# Relay_Schematic_w_headers.net
KiCad netlist of a schematic drawn in Altium Designer
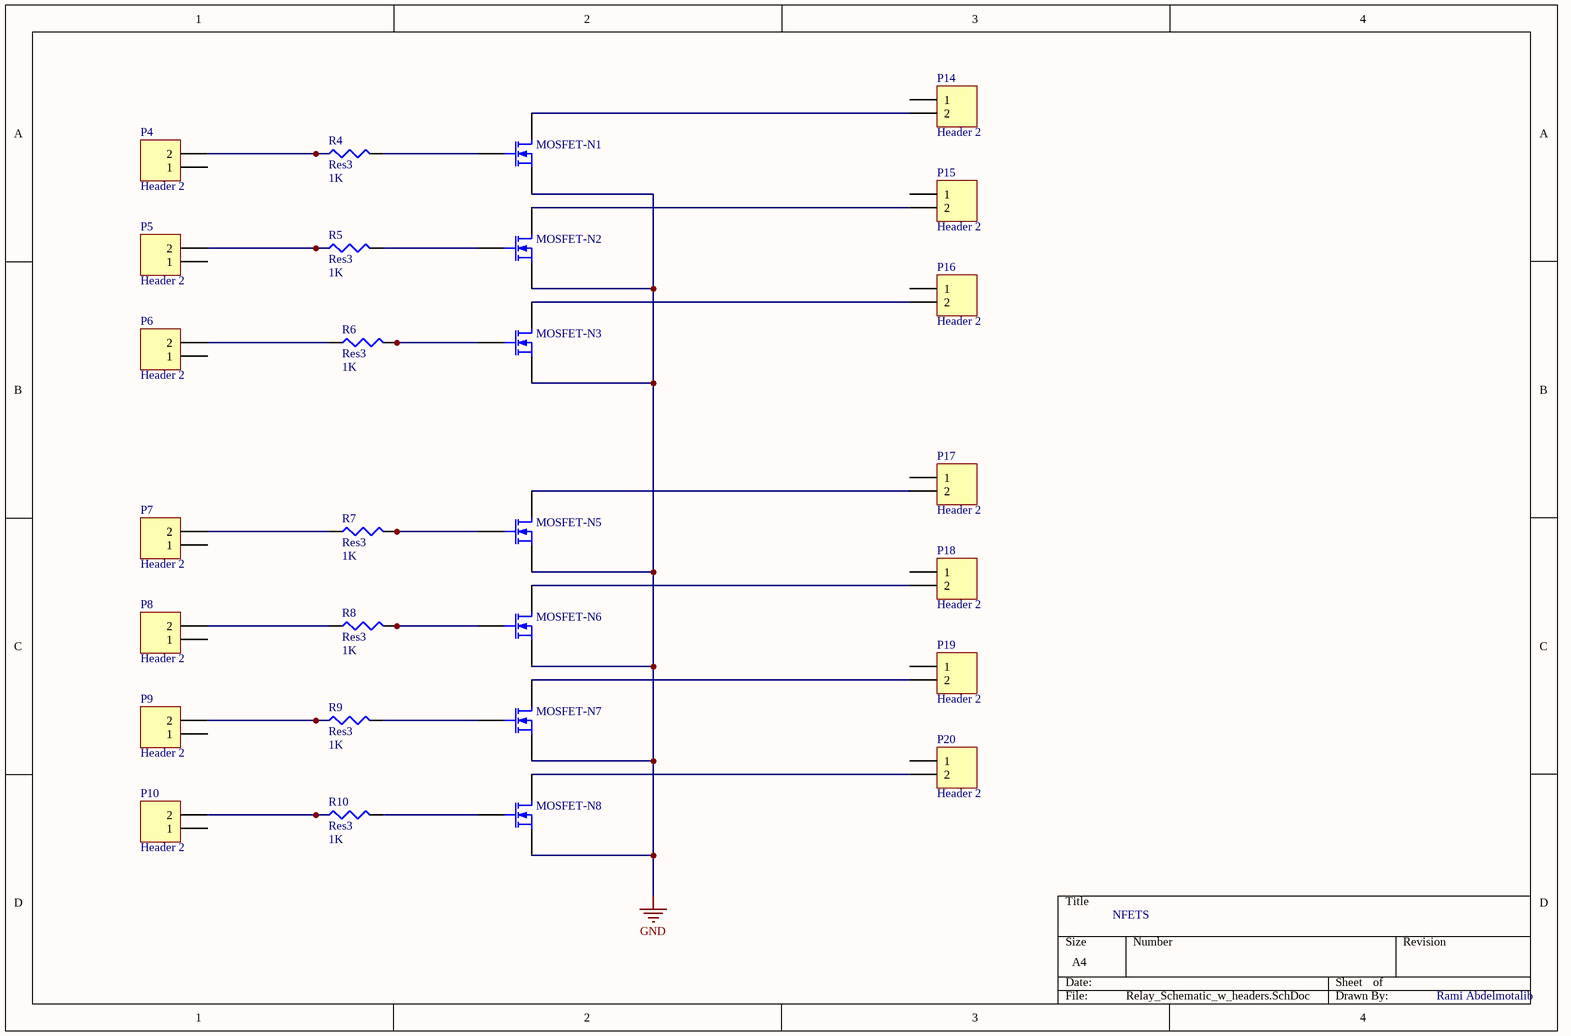
[diagram p0: Relay_Schematic_w_headers.SchDoc]

(export (version "E")
  (design (tool "Eeschema 10.0.6"))
  (components
    (comp (ref "MOSFET-N1")
      (value "~")
      (footprint "E3")
      (description "N-Channel MOSFET")
      (fields (field (name "PUBLISHER") "Altium Limited"))
      (libsource (lib "Miscellaneous Devices") (part "MOSFET-N"))
    )
    (comp (ref "MOSFET-N2")
      (value "~")
      (footprint "E3")
      (description "N-Channel MOSFET")
      (fields (field (name "PUBLISHER") "Altium Limited"))
      (libsource (lib "Miscellaneous Devices") (part "MOSFET-N"))
    )
    (comp (ref "MOSFET-N3")
      (value "~")
      (footprint "E3")
      (description "N-Channel MOSFET")
      (fields (field (name "PUBLISHER") "Altium Limited"))
      (libsource (lib "Miscellaneous Devices") (part "MOSFET-N"))
    )
    (comp (ref "MOSFET-N5")
      (value "~")
      (footprint "E3")
      (description "N-Channel MOSFET")
      (fields (field (name "PUBLISHER") "Altium Limited"))
      (libsource (lib "Miscellaneous Devices") (part "MOSFET-N"))
    )
    (comp (ref "MOSFET-N6")
      (value "~")
      (footprint "E3")
      (description "N-Channel MOSFET")
      (fields (field (name "PUBLISHER") "Altium Limited"))
      (libsource (lib "Miscellaneous Devices") (part "MOSFET-N"))
    )
    (comp (ref "MOSFET-N7")
      (value "~")
      (footprint "E3")
      (description "N-Channel MOSFET")
      (fields (field (name "PUBLISHER") "Altium Limited"))
      (libsource (lib "Miscellaneous Devices") (part "MOSFET-N"))
    )
    (comp (ref "MOSFET-N8")
      (value "~")
      (footprint "E3")
      (description "N-Channel MOSFET")
      (fields (field (name "PUBLISHER") "Altium Limited"))
      (libsource (lib "Miscellaneous Devices") (part "MOSFET-N"))
    )
    (comp (ref "P4")
      (value "Header 2")
      (footprint "HDR1X2")
      (description "Header, 2-Pin")
      (fields (field (name "PUBLISHER") "Altium Limited"))
      (libsource (lib "Miscellaneous Connectors") (part "Header 2"))
    )
    (comp (ref "P5")
      (value "Header 2")
      (footprint "HDR1X2")
      (description "Header, 2-Pin")
      (fields (field (name "PUBLISHER") "Altium Limited"))
      (libsource (lib "Miscellaneous Connectors") (part "Header 2"))
    )
    (comp (ref "P6")
      (value "Header 2")
      (footprint "HDR1X2")
      (description "Header, 2-Pin")
      (fields (field (name "PUBLISHER") "Altium Limited"))
      (libsource (lib "Miscellaneous Connectors") (part "Header 2"))
    )
    (comp (ref "P7")
      (value "Header 2")
      (footprint "HDR1X2")
      (description "Header, 2-Pin")
      (fields (field (name "PUBLISHER") "Altium Limited"))
      (libsource (lib "Miscellaneous Connectors") (part "Header 2"))
    )
    (comp (ref "P8")
      (value "Header 2")
      (footprint "HDR1X2")
      (description "Header, 2-Pin")
      (fields (field (name "PUBLISHER") "Altium Limited"))
      (libsource (lib "Miscellaneous Connectors") (part "Header 2"))
    )
    (comp (ref "P9")
      (value "Header 2")
      (footprint "HDR1X2")
      (description "Header, 2-Pin")
      (fields (field (name "PUBLISHER") "Altium Limited"))
      (libsource (lib "Miscellaneous Connectors") (part "Header 2"))
    )
    (comp (ref "P10")
      (value "Header 2")
      (footprint "HDR1X2")
      (description "Header, 2-Pin")
      (fields (field (name "PUBLISHER") "Altium Limited"))
      (libsource (lib "Miscellaneous Connectors") (part "Header 2"))
    )
    (comp (ref "P14")
      (value "Header 2")
      (footprint "HDR1X2")
      (description "Header, 2-Pin")
      (fields (field (name "PUBLISHER") "Altium Limited"))
      (libsource (lib "") (part "Header 2_1"))
    )
    (comp (ref "P15")
      (value "Header 2")
      (footprint "HDR1X2")
      (description "Header, 2-Pin")
      (fields (field (name "PUBLISHER") "Altium Limited"))
      (libsource (lib "") (part "Header 2_1"))
    )
    (comp (ref "P16")
      (value "Header 2")
      (footprint "HDR1X2")
      (description "Header, 2-Pin")
      (fields (field (name "PUBLISHER") "Altium Limited"))
      (libsource (lib "") (part "Header 2_1"))
    )
    (comp (ref "P17")
      (value "Header 2")
      (footprint "HDR1X2")
      (description "Header, 2-Pin")
      (fields (field (name "PUBLISHER") "Altium Limited"))
      (libsource (lib "") (part "Header 2_1"))
    )
    (comp (ref "P18")
      (value "Header 2")
      (footprint "HDR1X2")
      (description "Header, 2-Pin")
      (fields (field (name "PUBLISHER") "Altium Limited"))
      (libsource (lib "") (part "Header 2_1"))
    )
    (comp (ref "P19")
      (value "Header 2")
      (footprint "HDR1X2")
      (description "Header, 2-Pin")
      (fields (field (name "PUBLISHER") "Altium Limited"))
      (libsource (lib "") (part "Header 2_1"))
    )
    (comp (ref "P20")
      (value "Header 2")
      (footprint "HDR1X2")
      (description "Header, 2-Pin")
      (fields (field (name "PUBLISHER") "Altium Limited"))
      (libsource (lib "") (part "Header 2_1"))
    )
    (comp (ref "R4")
      (value "Res3")
      (footprint "14-1210")
      (description "Resistor")
      (fields (field (name "ALTIUM_VALUE") "1K") (field (name "PUBLISHER") "Altium Limited"))
      (libsource (lib "Miscellaneous Devices") (part "Res3"))
    )
    (comp (ref "R5")
      (value "Res3")
      (footprint "14-1210")
      (description "Resistor")
      (fields (field (name "ALTIUM_VALUE") "1K") (field (name "PUBLISHER") "Altium Limited"))
      (libsource (lib "Miscellaneous Devices") (part "Res3"))
    )
    (comp (ref "R6")
      (value "Res3")
      (footprint "14-1210")
      (description "Resistor")
      (fields (field (name "ALTIUM_VALUE") "1K") (field (name "PUBLISHER") "Altium Limited"))
      (libsource (lib "Miscellaneous Devices") (part "Res3"))
    )
    (comp (ref "R7")
      (value "Res3")
      (footprint "14-1210")
      (description "Resistor")
      (fields (field (name "ALTIUM_VALUE") "1K") (field (name "PUBLISHER") "Altium Limited"))
      (libsource (lib "Miscellaneous Devices") (part "Res3"))
    )
    (comp (ref "R8")
      (value "Res3")
      (footprint "14-1210")
      (description "Resistor")
      (fields (field (name "ALTIUM_VALUE") "1K") (field (name "PUBLISHER") "Altium Limited"))
      (libsource (lib "Miscellaneous Devices") (part "Res3"))
    )
    (comp (ref "R9")
      (value "Res3")
      (footprint "14-1210")
      (description "Resistor")
      (fields (field (name "ALTIUM_VALUE") "1K") (field (name "PUBLISHER") "Altium Limited"))
      (libsource (lib "Miscellaneous Devices") (part "Res3"))
    )
    (comp (ref "R10")
      (value "Res3")
      (footprint "14-1210")
      (description "Resistor")
      (fields (field (name "ALTIUM_VALUE") "1K") (field (name "PUBLISHER") "Altium Limited"))
      (libsource (lib "Miscellaneous Devices") (part "Res3"))
    )
  )
  (nets
    (net (code "1") (name "GND") (class "Default")
      (node (ref "MOSFET-N1") (pin "3") (pinfunction "S_3") (pintype "passive"))
      (node (ref "MOSFET-N2") (pin "3") (pinfunction "S_3") (pintype "passive"))
      (node (ref "MOSFET-N3") (pin "3") (pinfunction "S_3") (pintype "passive"))
      (node (ref "MOSFET-N5") (pin "3") (pinfunction "S_3") (pintype "passive"))
      (node (ref "MOSFET-N6") (pin "3") (pinfunction "S_3") (pintype "passive"))
      (node (ref "MOSFET-N7") (pin "3") (pinfunction "S_3") (pintype "passive"))
      (node (ref "MOSFET-N8") (pin "3") (pinfunction "S_3") (pintype "passive"))
    )
    (net (code "2") (name "Net-(MOSFET-N1-D)") (class "Default")
      (node (ref "MOSFET-N1") (pin "1") (pinfunction "D_1") (pintype "passive"))
      (node (ref "P14") (pin "2") (pinfunction "2_2") (pintype "passive"))
    )
    (net (code "3") (name "Net-(MOSFET-N1-G)") (class "Default")
      (node (ref "MOSFET-N1") (pin "2") (pinfunction "G_2") (pintype "passive"))
      (node (ref "R4") (pin "2") (pinfunction "2_2") (pintype "passive"))
    )
    (net (code "4") (name "Net-(MOSFET-N2-D)") (class "Default")
      (node (ref "MOSFET-N2") (pin "1") (pinfunction "D_1") (pintype "passive"))
      (node (ref "P15") (pin "2") (pinfunction "2_2") (pintype "passive"))
    )
    (net (code "5") (name "Net-(MOSFET-N2-G)") (class "Default")
      (node (ref "MOSFET-N2") (pin "2") (pinfunction "G_2") (pintype "passive"))
      (node (ref "R5") (pin "2") (pinfunction "2_2") (pintype "passive"))
    )
    (net (code "6") (name "Net-(MOSFET-N3-D)") (class "Default")
      (node (ref "MOSFET-N3") (pin "1") (pinfunction "D_1") (pintype "passive"))
      (node (ref "P16") (pin "2") (pinfunction "2_2") (pintype "passive"))
    )
    (net (code "7") (name "Net-(MOSFET-N3-G)") (class "Default")
      (node (ref "MOSFET-N3") (pin "2") (pinfunction "G_2") (pintype "passive"))
      (node (ref "R6") (pin "2") (pinfunction "2_2") (pintype "passive"))
    )
    (net (code "8") (name "Net-(MOSFET-N5-D)") (class "Default")
      (node (ref "MOSFET-N5") (pin "1") (pinfunction "D_1") (pintype "passive"))
      (node (ref "P17") (pin "2") (pinfunction "2_2") (pintype "passive"))
    )
    (net (code "9") (name "Net-(MOSFET-N5-G)") (class "Default")
      (node (ref "MOSFET-N5") (pin "2") (pinfunction "G_2") (pintype "passive"))
      (node (ref "R7") (pin "2") (pinfunction "2_2") (pintype "passive"))
    )
    (net (code "10") (name "Net-(MOSFET-N6-D)") (class "Default")
      (node (ref "MOSFET-N6") (pin "1") (pinfunction "D_1") (pintype "passive"))
      (node (ref "P18") (pin "2") (pinfunction "2_2") (pintype "passive"))
    )
    (net (code "11") (name "Net-(MOSFET-N6-G)") (class "Default")
      (node (ref "MOSFET-N6") (pin "2") (pinfunction "G_2") (pintype "passive"))
      (node (ref "R8") (pin "2") (pinfunction "2_2") (pintype "passive"))
    )
    (net (code "12") (name "Net-(MOSFET-N7-D)") (class "Default")
      (node (ref "MOSFET-N7") (pin "1") (pinfunction "D_1") (pintype "passive"))
      (node (ref "P19") (pin "2") (pinfunction "2_2") (pintype "passive"))
    )
    (net (code "13") (name "Net-(MOSFET-N7-G)") (class "Default")
      (node (ref "MOSFET-N7") (pin "2") (pinfunction "G_2") (pintype "passive"))
      (node (ref "R9") (pin "2") (pinfunction "2_2") (pintype "passive"))
    )
    (net (code "14") (name "Net-(MOSFET-N8-D)") (class "Default")
      (node (ref "MOSFET-N8") (pin "1") (pinfunction "D_1") (pintype "passive"))
      (node (ref "P20") (pin "2") (pinfunction "2_2") (pintype "passive"))
    )
    (net (code "15") (name "Net-(MOSFET-N8-G)") (class "Default")
      (node (ref "MOSFET-N8") (pin "2") (pinfunction "G_2") (pintype "passive"))
      (node (ref "R10") (pin "2") (pinfunction "2_2") (pintype "passive"))
    )
    (net (code "16") (name "Net-(P4-Pad2)") (class "Default")
      (node (ref "P4") (pin "2") (pinfunction "2_2") (pintype "passive"))
      (node (ref "R4") (pin "1") (pinfunction "1_1") (pintype "passive"))
    )
    (net (code "17") (name "Net-(P5-Pad2)") (class "Default")
      (node (ref "P5") (pin "2") (pinfunction "2_2") (pintype "passive"))
      (node (ref "R5") (pin "1") (pinfunction "1_1") (pintype "passive"))
    )
    (net (code "18") (name "Net-(P6-Pad2)") (class "Default")
      (node (ref "P6") (pin "2") (pinfunction "2_2") (pintype "passive"))
      (node (ref "R6") (pin "1") (pinfunction "1_1") (pintype "passive"))
    )
    (net (code "19") (name "Net-(P7-Pad2)") (class "Default")
      (node (ref "P7") (pin "2") (pinfunction "2_2") (pintype "passive"))
      (node (ref "R7") (pin "1") (pinfunction "1_1") (pintype "passive"))
    )
    (net (code "20") (name "Net-(P8-Pad2)") (class "Default")
      (node (ref "P8") (pin "2") (pinfunction "2_2") (pintype "passive"))
      (node (ref "R8") (pin "1") (pinfunction "1_1") (pintype "passive"))
    )
    (net (code "21") (name "Net-(P9-Pad2)") (class "Default")
      (node (ref "P9") (pin "2") (pinfunction "2_2") (pintype "passive"))
      (node (ref "R9") (pin "1") (pinfunction "1_1") (pintype "passive"))
    )
    (net (code "22") (name "Net-(P10-Pad2)") (class "Default")
      (node (ref "P10") (pin "2") (pinfunction "2_2") (pintype "passive"))
      (node (ref "R10") (pin "1") (pinfunction "1_1") (pintype "passive"))
    )
    (net (code "23") (name "unconnected-(P4-Pad1)") (class "Default")
      (node (ref "P4") (pin "1") (pinfunction "1_1") (pintype "passive"))
    )
    (net (code "24") (name "unconnected-(P5-Pad1)") (class "Default")
      (node (ref "P5") (pin "1") (pinfunction "1_1") (pintype "passive"))
    )
    (net (code "25") (name "unconnected-(P6-Pad1)") (class "Default")
      (node (ref "P6") (pin "1") (pinfunction "1_1") (pintype "passive"))
    )
    (net (code "26") (name "unconnected-(P7-Pad1)") (class "Default")
      (node (ref "P7") (pin "1") (pinfunction "1_1") (pintype "passive"))
    )
    (net (code "27") (name "unconnected-(P8-Pad1)") (class "Default")
      (node (ref "P8") (pin "1") (pinfunction "1_1") (pintype "passive"))
    )
    (net (code "28") (name "unconnected-(P9-Pad1)") (class "Default")
      (node (ref "P9") (pin "1") (pinfunction "1_1") (pintype "passive"))
    )
    (net (code "29") (name "unconnected-(P10-Pad1)") (class "Default")
      (node (ref "P10") (pin "1") (pinfunction "1_1") (pintype "passive"))
    )
    (net (code "30") (name "unconnected-(P14-Pad1)") (class "Default")
      (node (ref "P14") (pin "1") (pinfunction "1_1") (pintype "passive"))
    )
    (net (code "31") (name "unconnected-(P15-Pad1)") (class "Default")
      (node (ref "P15") (pin "1") (pinfunction "1_1") (pintype "passive"))
    )
    (net (code "32") (name "unconnected-(P16-Pad1)") (class "Default")
      (node (ref "P16") (pin "1") (pinfunction "1_1") (pintype "passive"))
    )
    (net (code "33") (name "unconnected-(P17-Pad1)") (class "Default")
      (node (ref "P17") (pin "1") (pinfunction "1_1") (pintype "passive"))
    )
    (net (code "34") (name "unconnected-(P18-Pad1)") (class "Default")
      (node (ref "P18") (pin "1") (pinfunction "1_1") (pintype "passive"))
    )
    (net (code "35") (name "unconnected-(P19-Pad1)") (class "Default")
      (node (ref "P19") (pin "1") (pinfunction "1_1") (pintype "passive"))
    )
    (net (code "36") (name "unconnected-(P20-Pad1)") (class "Default")
      (node (ref "P20") (pin "1") (pinfunction "1_1") (pintype "passive"))
    )
  )
)
